# PIXRACER-SD-USB-R12.net
KiCad netlist of a schematic drawn in Altium Designer
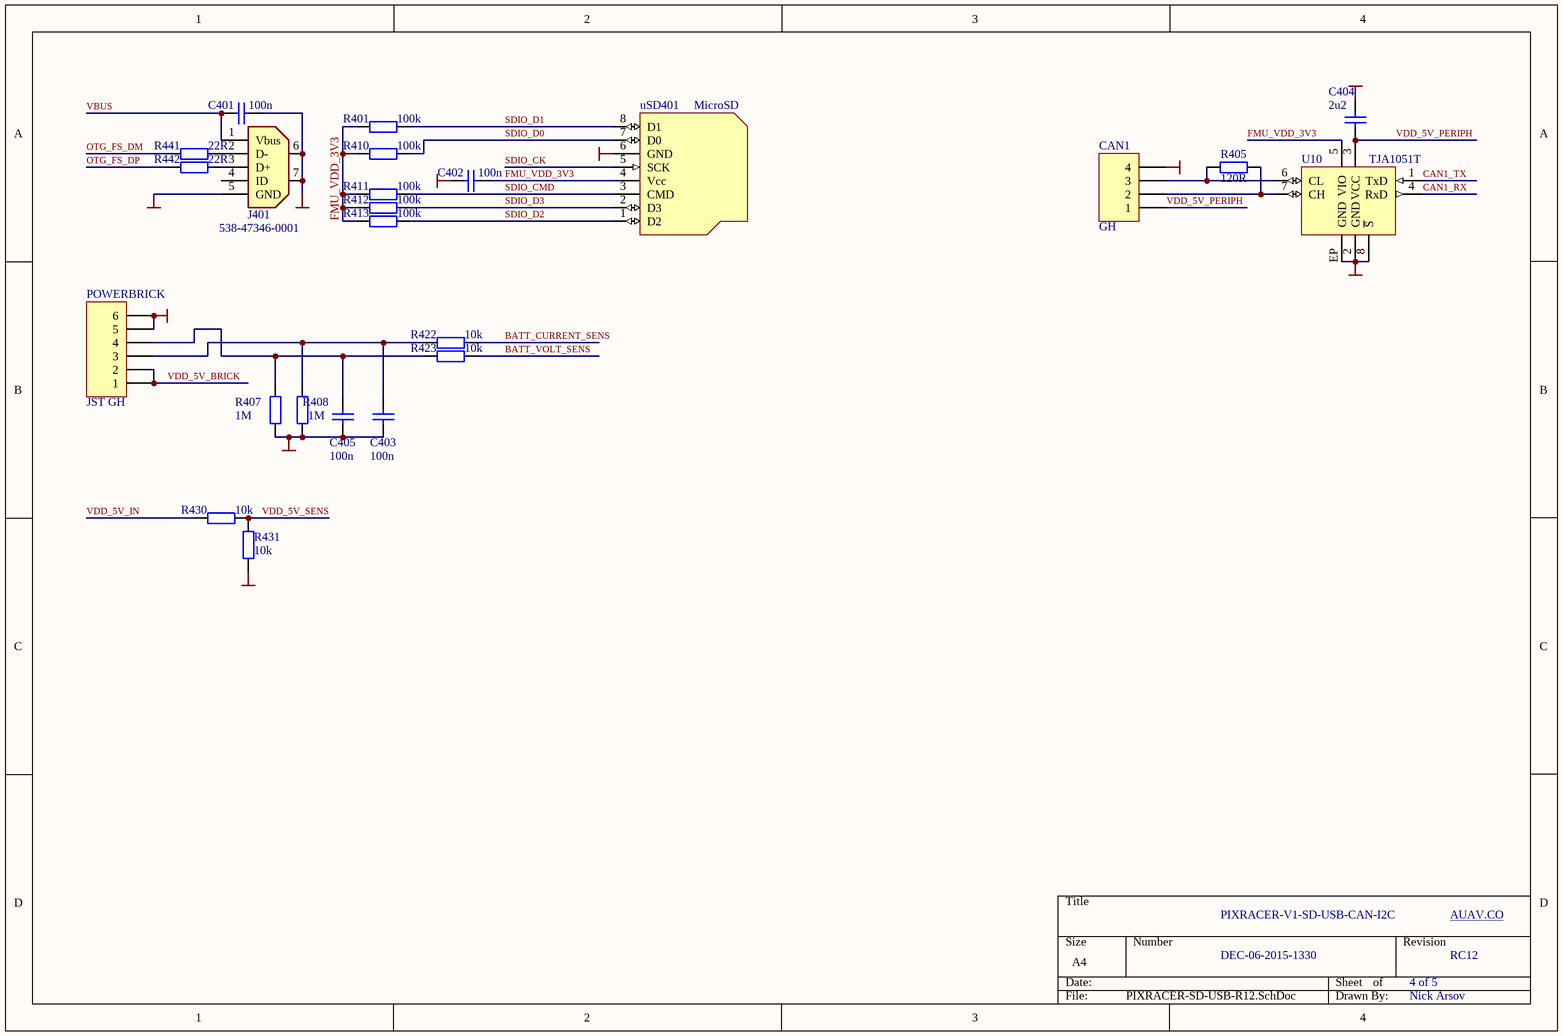
[diagram p0: PIXRACER-SD-USB-R12.SchDoc]

(export (version "E")
  (design (tool "Eeschema 10.0.6"))
  (components
    (comp (ref "C401")
      (value "100n")
      (footprint "0402A")
      (description "Capacitor")
      (fields (field (name "PUBLISHER") "Altium Limited"))
      (libsource (lib "Miscellaneous Devices") (part "Cap"))
    )
    (comp (ref "C402")
      (value "100n")
      (footprint "0402A")
      (description "Capacitor")
      (fields (field (name "PUBLISHER") "Altium Limited"))
      (libsource (lib "Miscellaneous Devices") (part "Cap"))
    )
    (comp (ref "C403")
      (value "100n")
      (footprint "0402A")
      (description "Capacitor")
      (fields (field (name "PUBLISHER") "Altium Limited"))
      (libsource (lib "Miscellaneous Devices") (part "Cap"))
    )
    (comp (ref "C404")
      (value "2u2")
      (footprint "0603A")
      (description "Capacitor")
      (fields (field (name "PUBLISHER") "Altium Limited"))
      (libsource (lib "Miscellaneous Devices") (part "Cap"))
    )
    (comp (ref "C405")
      (value "100n")
      (footprint "0402A")
      (description "Capacitor")
      (fields (field (name "PUBLISHER") "Altium Limited"))
      (libsource (lib "Miscellaneous Devices") (part "Cap"))
    )
    (comp (ref "CAN1")
      (value "GH")
      (footprint "Molex_1.25_click_4")
      (description "Header, 4-Pin")
      (fields (field (name "PUBLISHER") "Altium Limited"))
      (libsource (lib "Miscellaneous Connectors") (part "Header 4"))
    )
    (comp (ref "J401")
      (value "miniUSB")
      (footprint "USBmicro_B")
      (fields (field (name "MOUSER PART NUMBER") "538-47346-0001"))
      (libsource (lib "My_Altium") (part "MicroUSB"))
    )
    (comp (ref "POWERBRICK")
      (value "JST GH")
      (footprint "Molex_Clok_1.25_6H")
      (description "Header, 6-Pin")
      (fields (field (name "PUBLISHER") "Altium Limited"))
      (libsource (lib "Miscellaneous Connectors") (part "Header 6"))
    )
    (comp (ref "R401")
      (value "100k")
      (footprint "0402A")
      (description "Resistor")
      (fields (field (name "PUBLISHER") "Altium Limited"))
      (libsource (lib "Miscellaneous Devices") (part "Res2"))
    )
    (comp (ref "R405")
      (value "120R")
      (footprint "0603A")
      (description "Resistor")
      (fields (field (name "PUBLISHER") "Altium Limited"))
      (libsource (lib "Miscellaneous Devices") (part "Res2"))
    )
    (comp (ref "R407")
      (value "1M")
      (footprint "0402A")
      (description "Resistor")
      (fields (field (name "PUBLISHER") "Altium Limited"))
      (libsource (lib "") (part "Res2_1"))
    )
    (comp (ref "R408")
      (value "1M")
      (footprint "0402A")
      (description "Resistor")
      (fields (field (name "PUBLISHER") "Altium Limited"))
      (libsource (lib "") (part "Res2_1"))
    )
    (comp (ref "R410")
      (value "100k")
      (footprint "0402A")
      (description "Resistor")
      (fields (field (name "PUBLISHER") "Altium Limited"))
      (libsource (lib "Miscellaneous Devices") (part "Res2"))
    )
    (comp (ref "R411")
      (value "100k")
      (footprint "0402A")
      (description "Resistor")
      (fields (field (name "PUBLISHER") "Altium Limited"))
      (libsource (lib "Miscellaneous Devices") (part "Res2"))
    )
    (comp (ref "R412")
      (value "100k")
      (footprint "0402A")
      (description "Resistor")
      (fields (field (name "PUBLISHER") "Altium Limited"))
      (libsource (lib "Miscellaneous Devices") (part "Res2"))
    )
    (comp (ref "R413")
      (value "100k")
      (footprint "0402A")
      (description "Resistor")
      (fields (field (name "PUBLISHER") "Altium Limited"))
      (libsource (lib "Miscellaneous Devices") (part "Res2"))
    )
    (comp (ref "R422")
      (value "10k")
      (footprint "0402A")
      (description "Resistor")
      (fields (field (name "PUBLISHER") "Altium Limited"))
      (libsource (lib "Miscellaneous Devices") (part "Res2"))
    )
    (comp (ref "R423")
      (value "10k")
      (footprint "0402A")
      (description "Resistor")
      (fields (field (name "PUBLISHER") "Altium Limited"))
      (libsource (lib "Miscellaneous Devices") (part "Res2"))
    )
    (comp (ref "R430")
      (value "10k")
      (footprint "0402A")
      (description "Resistor")
      (fields (field (name "PUBLISHER") "Altium Limited"))
      (libsource (lib "Miscellaneous Devices") (part "Res2"))
    )
    (comp (ref "R431")
      (value "10k")
      (footprint "0402A")
      (description "Resistor")
      (fields (field (name "PUBLISHER") "Altium Limited"))
      (libsource (lib "") (part "Res2_1"))
    )
    (comp (ref "R441")
      (value "22R")
      (footprint "0402A")
      (description "Resistor")
      (fields (field (name "PUBLISHER") "Altium Limited"))
      (libsource (lib "Miscellaneous Devices") (part "Res2"))
    )
    (comp (ref "R442")
      (value "22R")
      (footprint "0402A")
      (description "Resistor")
      (fields (field (name "PUBLISHER") "Altium Limited"))
      (libsource (lib "Miscellaneous Devices") (part "Res2"))
    )
    (comp (ref "U10")
      (value "TJA1051T")
      (footprint "8DFN_3x3")
      (libsource (lib "My_Altium") (part "TJA1051T"))
    )
    (comp (ref "uSD401")
      (value "MicroSD")
      (footprint "MicroSD_China_01")
      (libsource (lib "My_Altium") (part "MicroSD"))
    )
  )
  (nets
    (net (code "1") (name "/BATT_CURRENT_SENS") (class "Default")
      (node (ref "R422") (pin "1") (pinfunction "1_1") (pintype "passive"))
    )
    (net (code "2") (name "/BATT_VOLT_SENS") (class "Default")
      (node (ref "R423") (pin "1") (pinfunction "1_1") (pintype "passive"))
    )
    (net (code "3") (name "/CAN1_RX") (class "Default")
      (node (ref "U10") (pin "4") (pinfunction "RxD_4") (pintype "output"))
    )
    (net (code "4") (name "/CAN1_TX") (class "Default")
      (node (ref "U10") (pin "1") (pinfunction "TxD_1") (pintype "input"))
    )
    (net (code "5") (name "/FMU_VDD_3V3") (class "Default")
      (node (ref "C402") (pin "1") (pinfunction "1_1") (pintype "passive"))
      (node (ref "R401") (pin "2") (pinfunction "2_2") (pintype "passive"))
      (node (ref "R410") (pin "2") (pinfunction "2_2") (pintype "passive"))
      (node (ref "R411") (pin "2") (pinfunction "2_2") (pintype "passive"))
      (node (ref "R412") (pin "2") (pinfunction "2_2") (pintype "passive"))
      (node (ref "R413") (pin "2") (pinfunction "2_2") (pintype "passive"))
      (node (ref "U10") (pin "5") (pinfunction "VIO_5") (pintype "power_in"))
      (node (ref "uSD401") (pin "4") (pinfunction "Vcc_4") (pintype "power_in"))
    )
    (net (code "6") (name "/OTG_FS_DM") (class "Default")
      (node (ref "R441") (pin "2") (pinfunction "2_2") (pintype "passive"))
    )
    (net (code "7") (name "/OTG_FS_DP") (class "Default")
      (node (ref "R442") (pin "2") (pinfunction "2_2") (pintype "passive"))
    )
    (net (code "8") (name "/SDIO_CK") (class "Default")
      (node (ref "uSD401") (pin "5") (pinfunction "SCK_5") (pintype "input"))
    )
    (net (code "9") (name "/SDIO_CMD") (class "Default")
      (node (ref "R411") (pin "1") (pinfunction "1_1") (pintype "passive"))
      (node (ref "uSD401") (pin "3") (pinfunction "CMD_3") (pintype "passive"))
    )
    (net (code "10") (name "/SDIO_D0") (class "Default")
      (node (ref "R410") (pin "1") (pinfunction "1_1") (pintype "passive"))
      (node (ref "uSD401") (pin "7") (pinfunction "D0_7") (pintype "bidirectional"))
    )
    (net (code "11") (name "/SDIO_D1") (class "Default")
      (node (ref "R401") (pin "1") (pinfunction "1_1") (pintype "passive"))
      (node (ref "uSD401") (pin "8") (pinfunction "D1_8") (pintype "bidirectional"))
    )
    (net (code "12") (name "/SDIO_D2") (class "Default")
      (node (ref "R413") (pin "1") (pinfunction "1_1") (pintype "passive"))
      (node (ref "uSD401") (pin "1") (pinfunction "D2_1") (pintype "bidirectional"))
    )
    (net (code "13") (name "/SDIO_D3") (class "Default")
      (node (ref "R412") (pin "1") (pinfunction "1_1") (pintype "passive"))
      (node (ref "uSD401") (pin "2") (pinfunction "D3_2") (pintype "bidirectional"))
    )
    (net (code "14") (name "/VBUS") (class "Default")
      (node (ref "C401") (pin "2") (pinfunction "2_2") (pintype "passive"))
      (node (ref "J401") (pin "1") (pinfunction "Vbus_1") (pintype "power_in"))
    )
    (net (code "15") (name "/VDD_5V_BRICK") (class "Default")
      (node (ref "POWERBRICK") (pin "1") (pinfunction "1_1") (pintype "passive"))
      (node (ref "POWERBRICK") (pin "2") (pinfunction "2_2") (pintype "passive"))
    )
    (net (code "16") (name "/VDD_5V_IN") (class "Default")
      (node (ref "R430") (pin "2") (pinfunction "2_2") (pintype "passive"))
    )
    (net (code "17") (name "/VDD_5V_PERIPH") (class "Default")
      (node (ref "C404") (pin "2") (pinfunction "2_2") (pintype "passive"))
      (node (ref "CAN1") (pin "1") (pinfunction "1_1") (pintype "passive"))
      (node (ref "U10") (pin "3") (pinfunction "VCC_3") (pintype "power_in"))
    )
    (net (code "18") (name "/VDD_5V_SENS") (class "Default")
      (node (ref "R430") (pin "1") (pinfunction "1_1") (pintype "passive"))
      (node (ref "R431") (pin "1") (pinfunction "1_1") (pintype "passive"))
    )
    (net (code "19") (name "GND") (class "Default")
      (node (ref "C401") (pin "1") (pinfunction "1_1") (pintype "passive"))
      (node (ref "C402") (pin "2") (pinfunction "2_2") (pintype "passive"))
      (node (ref "C403") (pin "2") (pinfunction "2_2") (pintype "passive"))
      (node (ref "C404") (pin "1") (pinfunction "1_1") (pintype "passive"))
      (node (ref "C405") (pin "2") (pinfunction "2_2") (pintype "passive"))
      (node (ref "CAN1") (pin "4") (pinfunction "4_4") (pintype "passive"))
      (node (ref "J401") (pin "5") (pinfunction "GND_5") (pintype "power_in"))
      (node (ref "J401") (pin "6") (pinfunction "GND_6") (pintype "passive"))
      (node (ref "J401") (pin "7") (pinfunction "GND_7") (pintype "passive"))
      (node (ref "POWERBRICK") (pin "5") (pinfunction "5_5") (pintype "passive"))
      (node (ref "POWERBRICK") (pin "6") (pinfunction "6_6") (pintype "passive"))
      (node (ref "R407") (pin "2") (pinfunction "2_2") (pintype "passive"))
      (node (ref "R408") (pin "2") (pinfunction "2_2") (pintype "passive"))
      (node (ref "R431") (pin "2") (pinfunction "2_2") (pintype "passive"))
      (node (ref "U10") (pin "2") (pinfunction "GND_2") (pintype "power_in"))
      (node (ref "U10") (pin "8") (pinfunction "~{S}_8") (pintype "passive"))
      (node (ref "U10") (pin "EP") (pinfunction "GND_EP") (pintype "power_in"))
      (node (ref "uSD401") (pin "6") (pinfunction "GND_6") (pintype "power_in"))
    )
    (net (code "20") (name "Net-(C403-Pad1)") (class "Default")
      (node (ref "C403") (pin "1") (pinfunction "1_1") (pintype "passive"))
      (node (ref "POWERBRICK") (pin "3") (pinfunction "3_3") (pintype "passive"))
      (node (ref "R408") (pin "1") (pinfunction "1_1") (pintype "passive"))
      (node (ref "R422") (pin "2") (pinfunction "2_2") (pintype "passive"))
    )
    (net (code "21") (name "Net-(C405-Pad1)") (class "Default")
      (node (ref "C405") (pin "1") (pinfunction "1_1") (pintype "passive"))
      (node (ref "POWERBRICK") (pin "4") (pinfunction "4_4") (pintype "passive"))
      (node (ref "R407") (pin "1") (pinfunction "1_1") (pintype "passive"))
      (node (ref "R423") (pin "2") (pinfunction "2_2") (pintype "passive"))
    )
    (net (code "22") (name "Net-(J401-D+)") (class "Default")
      (node (ref "J401") (pin "3") (pinfunction "D+_3") (pintype "passive"))
      (node (ref "R442") (pin "1") (pinfunction "1_1") (pintype "passive"))
    )
    (net (code "23") (name "Net-(J401-D-)") (class "Default")
      (node (ref "J401") (pin "2") (pinfunction "D-_2") (pintype "passive"))
      (node (ref "R441") (pin "1") (pinfunction "1_1") (pintype "passive"))
    )
    (net (code "24") (name "Net-(U10-CH)") (class "Default")
      (node (ref "CAN1") (pin "2") (pinfunction "2_2") (pintype "passive"))
      (node (ref "R405") (pin "1") (pinfunction "1_1") (pintype "passive"))
      (node (ref "U10") (pin "7") (pinfunction "CH_7") (pintype "bidirectional"))
    )
    (net (code "25") (name "Net-(U10-CL)") (class "Default")
      (node (ref "CAN1") (pin "3") (pinfunction "3_3") (pintype "passive"))
      (node (ref "R405") (pin "2") (pinfunction "2_2") (pintype "passive"))
      (node (ref "U10") (pin "6") (pinfunction "CL_6") (pintype "bidirectional"))
    )
    (net (code "26") (name "unconnected-(J401-ID-Pad4)") (class "Default")
      (node (ref "J401") (pin "4") (pinfunction "ID_4") (pintype "passive"))
    )
  )
)
